# powercast-breakout.net
KiCad netlist of a schematic drawn in EAGLE
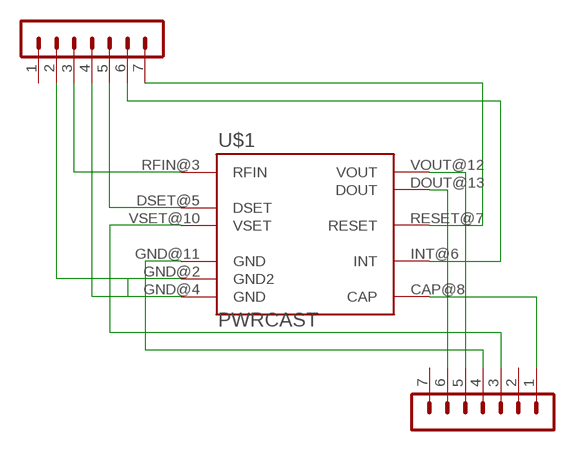
[diagram p0: schematic, sheet 1]

(export (version "E")
  (design (tool "Eeschema 10.0.6"))
  (components
    (comp (ref "S")
      (value "MA07-1OCTAGON-NS")
      (footprint "eagle-import:MA07-1-SMALL-NOSILK")
      (libsource (lib "eagle-import") (part "MA07-1OCTAGON-NS"))
    )
    (comp (ref "SV2")
      (value "MA07-1OCTAGON-NS")
      (footprint "eagle-import:MA07-1-SMALL-NOSILK")
      (libsource (lib "eagle-import") (part "MA07-1OCTAGON-NS"))
    )
    (comp (ref "U$1")
      (value "PWRCAST")
      (footprint "eagle-import:POWERCASTRCVMOD")
      (libsource (lib "eagle-import") (part "PWRCAST"))
    )
  )
  (nets
    (net (code "1") (name "Net-(SV2-Pad4)") (class "Default")
      (node (ref "SV2") (pin "4") (pinfunction "4_4") (pintype "passive"))
      (node (ref "U$1") (pin "GND@11") (pinfunction "GND_GND@11") (pintype "power_in"))
    )
    (net (code "2") (name "Net-(U$1-CAP)") (class "Default")
      (node (ref "SV2") (pin "1") (pinfunction "1_1") (pintype "passive"))
      (node (ref "U$1") (pin "CAP@8") (pinfunction "CAP_CAP@8") (pintype "power_in"))
    )
    (net (code "3") (name "Net-(U$1-DOUT)") (class "Default")
      (node (ref "SV2") (pin "6") (pinfunction "6_6") (pintype "passive"))
      (node (ref "U$1") (pin "DOUT@13") (pinfunction "DOUT_DOUT@13") (pintype "bidirectional"))
    )
    (net (code "4") (name "Net-(U$1-DSET)") (class "Default")
      (node (ref "S") (pin "5") (pinfunction "5_5") (pintype "passive"))
      (node (ref "U$1") (pin "DSET@5") (pinfunction "DSET_DSET@5") (pintype "bidirectional"))
    )
    (net (code "5") (name "Net-(U$1-GND2)") (class "Default")
      (node (ref "S") (pin "2") (pinfunction "2_2") (pintype "passive"))
      (node (ref "S") (pin "4") (pinfunction "4_4") (pintype "passive"))
      (node (ref "U$1") (pin "GND@2") (pinfunction "GND2_GND@2") (pintype "power_in"))
      (node (ref "U$1") (pin "GND@4") (pinfunction "GND_GND@4") (pintype "power_in"))
    )
    (net (code "6") (name "Net-(U$1-INT)") (class "Default")
      (node (ref "S") (pin "6") (pinfunction "6_6") (pintype "passive"))
      (node (ref "U$1") (pin "INT@6") (pinfunction "INT_INT@6") (pintype "output"))
    )
    (net (code "7") (name "Net-(U$1-RESET)") (class "Default")
      (node (ref "S") (pin "7") (pinfunction "7_7") (pintype "passive"))
      (node (ref "U$1") (pin "RESET@7") (pinfunction "RESET_RESET@7") (pintype "input"))
    )
    (net (code "8") (name "Net-(U$1-RFIN)") (class "Default")
      (node (ref "S") (pin "3") (pinfunction "3_3") (pintype "passive"))
      (node (ref "U$1") (pin "RFIN@3") (pinfunction "RFIN_RFIN@3") (pintype "power_in"))
    )
    (net (code "9") (name "Net-(U$1-VOUT)") (class "Default")
      (node (ref "SV2") (pin "5") (pinfunction "5_5") (pintype "passive"))
      (node (ref "U$1") (pin "VOUT@12") (pinfunction "VOUT_VOUT@12") (pintype "power_in"))
    )
    (net (code "10") (name "Net-(U$1-VSET)") (class "Default")
      (node (ref "SV2") (pin "3") (pinfunction "3_3") (pintype "passive"))
      (node (ref "U$1") (pin "VSET@10") (pinfunction "VSET_VSET@10") (pintype "bidirectional"))
    )
    (net (code "11") (name "unconnected-(S-Pad1)") (class "Default")
      (node (ref "S") (pin "1") (pinfunction "1_1") (pintype "passive"))
    )
    (net (code "12") (name "unconnected-(SV2-Pad2)") (class "Default")
      (node (ref "SV2") (pin "2") (pinfunction "2_2") (pintype "passive"))
    )
    (net (code "13") (name "unconnected-(SV2-Pad7)") (class "Default")
      (node (ref "SV2") (pin "7") (pinfunction "7_7") (pintype "passive"))
    )
  )
)
